# Power.net
KiCad netlist of a schematic drawn in Altium Designer
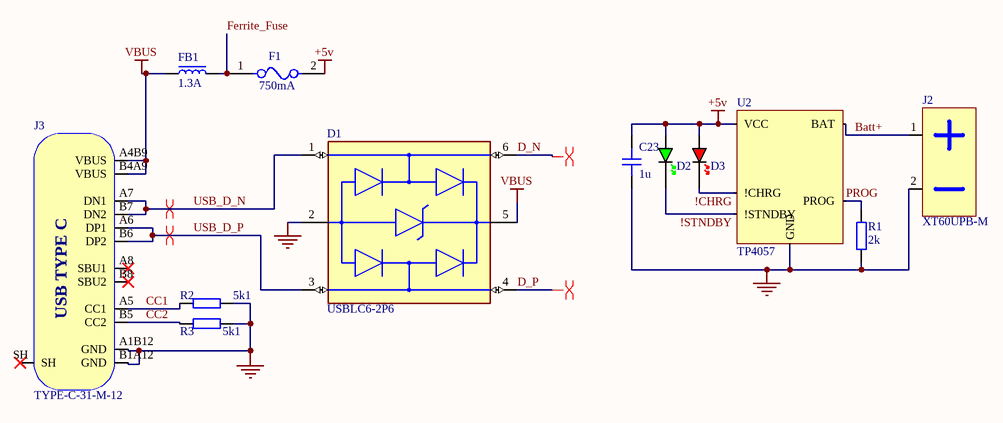
[diagram p0: Power.SchDoc]

(export (version "E")
  (design (tool "Eeschema 10.0.6"))
  (components
    (comp (ref "C23")
      (value "1u")
      (footprint "CAP_0402")
      (libsource (lib "Schematic-Lib-PhilsLab") (part "CAP_0402_25V"))
    )
    (comp (ref "D1")
      (value "USBLC6-2P6")
      (footprint "FP-SOT-666-MFG")
      (description "TVS DIODE 5.25V 17V SOT666")
      (libsource (lib "Altium Content Vault") (part "c871e55f7e3243d341edbd671b98d92"))
    )
    (comp (ref "D2")
      (value "GREEN")
      (footprint "LED_0603_GREEN")
      (description "LED 0603 GREEN SMD")
      (libsource (lib "Schematic-Lib-PhilsLab") (part "LED_0603_GREEN"))
    )
    (comp (ref "D3")
      (value "RED")
      (footprint "LED_0603_RED")
      (description "LED 0603 RED SMD")
      (libsource (lib "Schematic-Lib-PhilsLab") (part "LED_0603_RED"))
    )
    (comp (ref "F1")
      (value "750mA")
      (footprint "FP-SF-0603S-MFG")
      (description "FUSE BOARD MNT 500MA 50VDC 0603")
      (fields
        (field (name "MANUFACTURER") "Bourns Inc.")
        (field (name "MANUFACTURER PART NUMBER") "SF-0603S050-2")
      )
      (libsource (lib "Altium Content Vault") (part "5bcf9b9f640e542cf0359d10258e979"))
    )
    (comp (ref "FB1")
      (value "1.3A")
      (footprint "FB_0402")
      (description "Ferrite Bead SMD 0402")
      (libsource (lib "Schematic-Lib-PhilsLab") (part "FB_0402"))
    )
    (comp (ref "J2")
      (value "XT60UPB-M")
      (footprint "XT60UPB-M")
      (description "XT60 vertical male 2-pin AMASS")
      (fields (field (name "MANUFACTURER") "AMASS"))
      (libsource (lib "Schematic-Lib-PhilsLab") (part "XT60UPB-M"))
    )
    (comp (ref "J3")
      (value "TYPE-C-31-M-12")
      (footprint "TYPE-C-31-M-12")
      (description "USB Type C Connector Horizontal SMT")
      (fields (field (name "MANUFACTURER") "Koren Hroparts"))
      (libsource (lib "Schematic-Lib-PhilsLab") (part "TYPE-C-31-M-12"))
    )
    (comp (ref "R1")
      (value "2k")
      (footprint "RES_0402")
      (description "Resistor SMD 0402")
      (libsource (lib "Schematic-Lib-PhilsLab") (part "RES_0402"))
    )
    (comp (ref "R2")
      (value "5k1")
      (footprint "RES_0402")
      (description "Resistor SMD 0402")
      (libsource (lib "Schematic-Lib-PhilsLab") (part "RES_0402"))
    )
    (comp (ref "R3")
      (value "5k1")
      (footprint "RES_0402")
      (description "Resistor SMD 0402")
      (libsource (lib "Schematic-Lib-PhilsLab") (part "RES_0402"))
    )
    (comp (ref "U2")
      (value "TP4057")
      (footprint "SOT23-6")
      (libsource (lib "custom_symbols") (part "TP4057"))
    )
  )
  (nets
    (net (code "1") (name "+5v") (class "Default")
      (node (ref "C23") (pin "2") (pinfunction "2_2") (pintype "passive"))
      (node (ref "D2") (pin "A") (pinfunction "A_A") (pintype "passive"))
      (node (ref "D3") (pin "A") (pinfunction "A_A") (pintype "passive"))
      (node (ref "F1") (pin "2") (pinfunction "2_2") (pintype "passive"))
      (node (ref "U2") (pin "4") (pinfunction "VCC_4") (pintype "passive"))
    )
    (net (code "2") (name "/!CHRG") (class "Default")
      (node (ref "D3") (pin "K") (pinfunction "K_K") (pintype "passive"))
      (node (ref "U2") (pin "1") (pinfunction "!CHRG_1") (pintype "passive"))
    )
    (net (code "3") (name "/!STNDBY") (class "Default")
      (node (ref "D2") (pin "K") (pinfunction "K_K") (pintype "passive"))
      (node (ref "U2") (pin "5") (pinfunction "!STNDBY_5") (pintype "passive"))
    )
    (net (code "4") (name "/Batt+") (class "Default")
      (node (ref "J2") (pin "1") (pinfunction "V+_1") (pintype "power_in"))
      (node (ref "U2") (pin "3") (pinfunction "BAT_3") (pintype "passive"))
    )
    (net (code "5") (name "/CC1") (class "Default")
      (node (ref "J3") (pin "A5") (pinfunction "CC1_A5") (pintype "passive"))
      (node (ref "R2") (pin "1") (pinfunction "1_1") (pintype "passive"))
    )
    (net (code "6") (name "/CC2") (class "Default")
      (node (ref "J3") (pin "B5") (pinfunction "CC2_B5") (pintype "tri_state"))
      (node (ref "R3") (pin "1") (pinfunction "1_1") (pintype "passive"))
    )
    (net (code "7") (name "/D_N") (class "Default")
      (node (ref "D1") (pin "6") (pinfunction "I/O1_6") (pintype "bidirectional"))
    )
    (net (code "8") (name "/D_P") (class "Default")
      (node (ref "D1") (pin "4") (pinfunction "I/O2_4") (pintype "bidirectional"))
    )
    (net (code "9") (name "/Ferrite_Fuse") (class "Default")
      (node (ref "F1") (pin "1") (pinfunction "1_1") (pintype "passive"))
      (node (ref "FB1") (pin "2") (pinfunction "2_2") (pintype "passive"))
    )
    (net (code "10") (name "/PROG") (class "Default")
      (node (ref "R1") (pin "2") (pinfunction "2_2") (pintype "passive"))
      (node (ref "U2") (pin "6") (pinfunction "PROG_6") (pintype "passive"))
    )
    (net (code "11") (name "/USB_D_N") (class "Default")
      (node (ref "D1") (pin "1") (pinfunction "I/O1_1") (pintype "bidirectional"))
      (node (ref "J3") (pin "A7") (pinfunction "DN1_A7") (pintype "bidirectional"))
      (node (ref "J3") (pin "B7") (pinfunction "DN2_B7") (pintype "bidirectional"))
    )
    (net (code "12") (name "/USB_D_P") (class "Default")
      (node (ref "D1") (pin "3") (pinfunction "I/O2_3") (pintype "bidirectional"))
      (node (ref "J3") (pin "A6") (pinfunction "DP1_A6") (pintype "bidirectional"))
      (node (ref "J3") (pin "B6") (pinfunction "DP2_B6") (pintype "bidirectional"))
    )
    (net (code "13") (name "GND") (class "Default")
      (node (ref "C23") (pin "1") (pinfunction "1_1") (pintype "passive"))
      (node (ref "D1") (pin "2") (pinfunction "GND_2") (pintype "power_in"))
      (node (ref "J2") (pin "2") (pinfunction "V-_2") (pintype "power_in"))
      (node (ref "J3") (pin "A1B12") (pinfunction "GND_A1B12") (pintype "power_in"))
      (node (ref "J3") (pin "B1A12") (pinfunction "GND_B1A12") (pintype "power_in"))
      (node (ref "R1") (pin "1") (pinfunction "1_1") (pintype "passive"))
      (node (ref "R2") (pin "2") (pinfunction "2_2") (pintype "passive"))
      (node (ref "R3") (pin "2") (pinfunction "2_2") (pintype "passive"))
      (node (ref "U2") (pin "2") (pinfunction "GND_2") (pintype "passive"))
    )
    (net (code "14") (name "VBUS") (class "Default")
      (node (ref "D1") (pin "5") (pinfunction "VBUS_5") (pintype "power_in"))
      (node (ref "FB1") (pin "1") (pinfunction "1_1") (pintype "passive"))
      (node (ref "J3") (pin "A4B9") (pinfunction "VBUS_A4B9") (pintype "power_in"))
      (node (ref "J3") (pin "B4A9") (pinfunction "VBUS_B4A9") (pintype "power_in"))
    )
    (net (code "15") (name "unconnected-(J3-PadSH)") (class "Default")
      (node (ref "J3") (pin "SH") (pinfunction "SH_SH") (pintype "power_in+no_connect"))
    )
    (net (code "16") (name "unconnected-(J3-SBU1-PadA8)") (class "Default")
      (node (ref "J3") (pin "A8") (pinfunction "SBU1_A8") (pintype "bidirectional+no_connect"))
    )
    (net (code "17") (name "unconnected-(J3-SBU2-PadB8)") (class "Default")
      (node (ref "J3") (pin "B8") (pinfunction "SBU2_B8") (pintype "bidirectional+no_connect"))
    )
  )
)
